# Keg_Cop.net
KiCad netlist of a schematic drawn in EAGLE
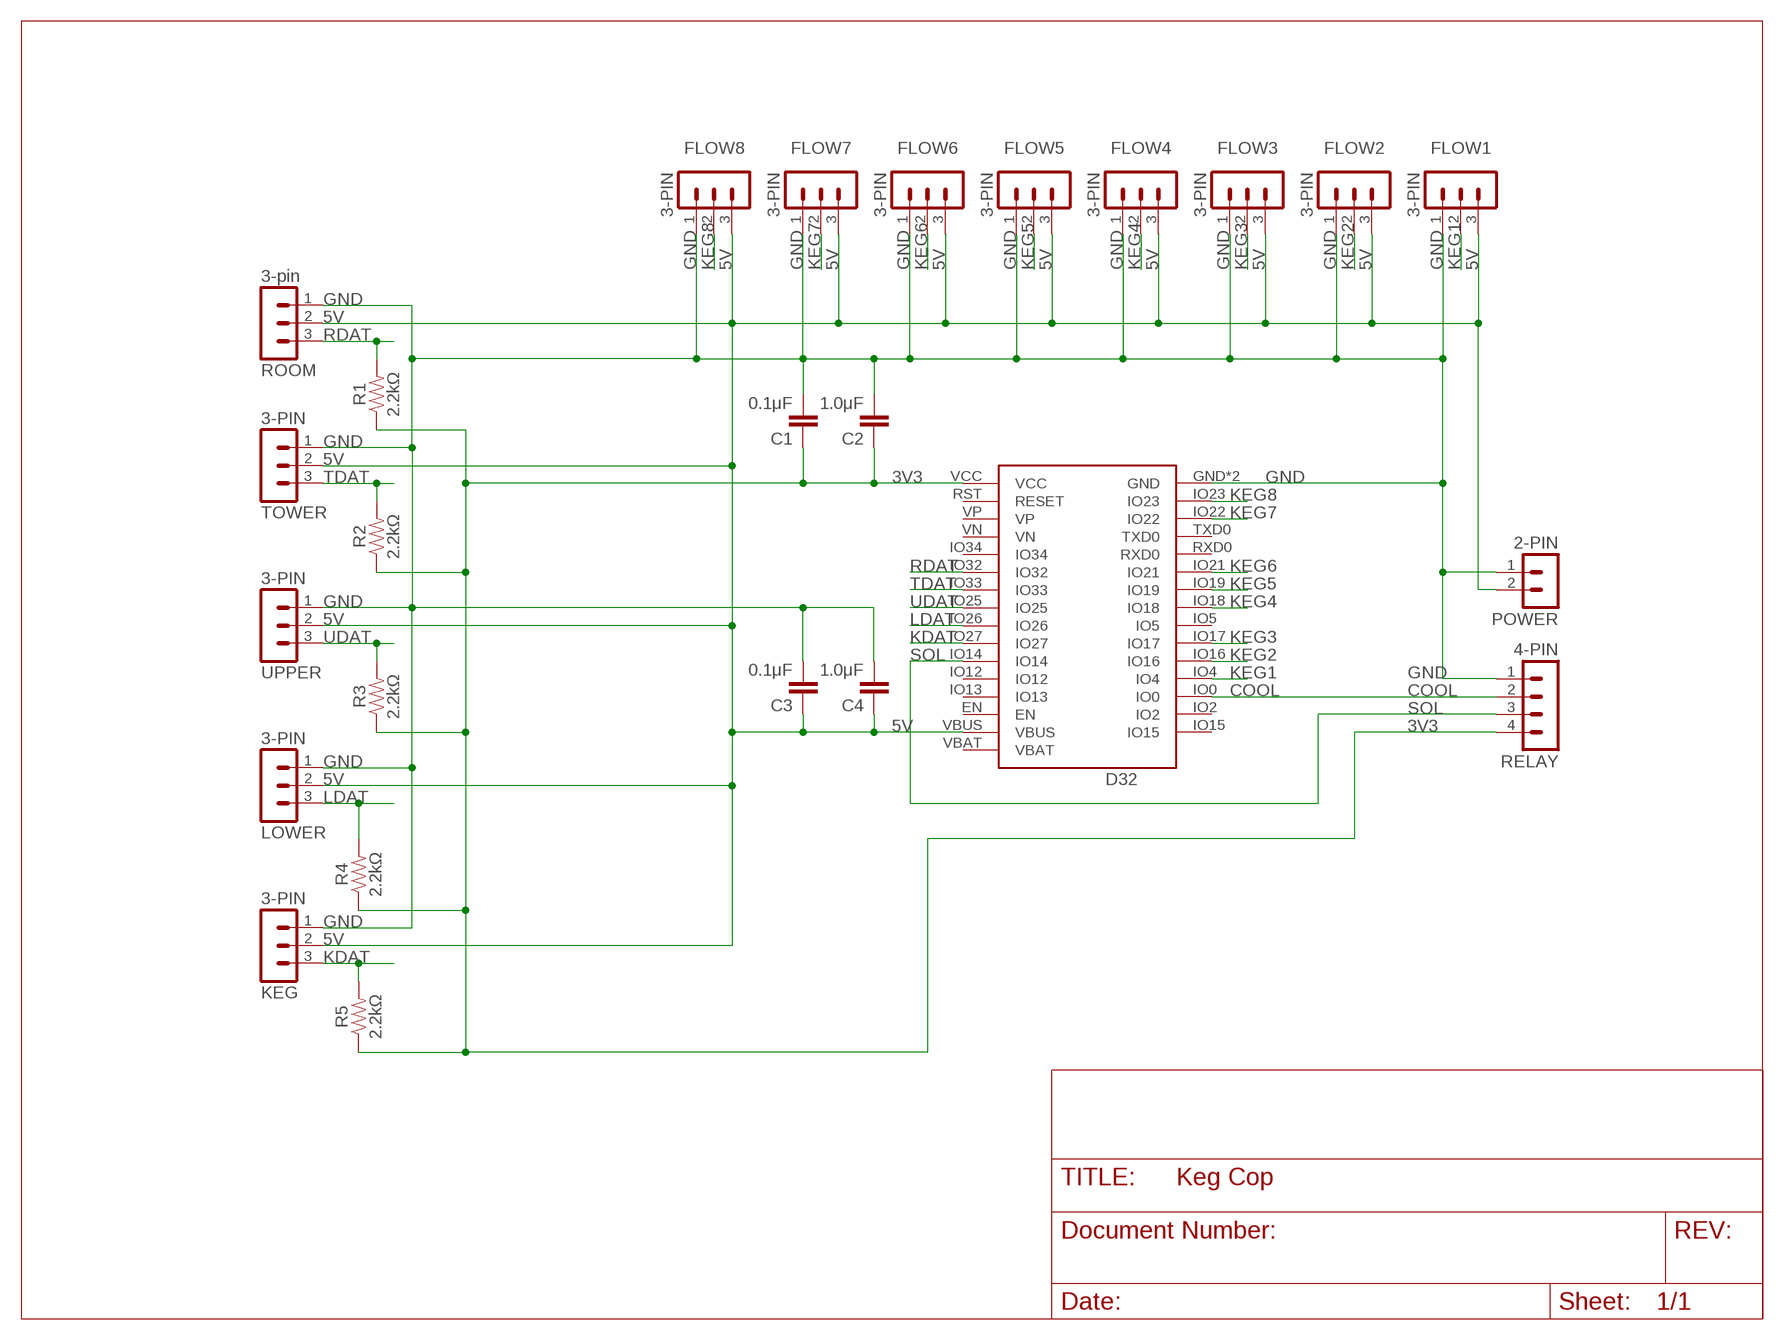
[diagram p0: schematic, sheet 1]

(export (version "E")
  (design (tool "Eeschema 10.0.6"))
  (components
    (comp (ref "C1")
      (value "0.1μF")
      (footprint "eagle-import:CAP_PTH-2.54")
      (libsource (lib "eagle-import") (part "CAP_CERAMIC_2.54"))
    )
    (comp (ref "C2")
      (value "1.0μF")
      (footprint "eagle-import:CAP_PTH-2.54")
      (libsource (lib "eagle-import") (part "CAP_CERAMIC_2.54"))
    )
    (comp (ref "C3")
      (value "0.1μF")
      (footprint "eagle-import:CAP_PTH-2.54")
      (libsource (lib "eagle-import") (part "CAP_CERAMIC_2.54"))
    )
    (comp (ref "C4")
      (value "1.0μF")
      (footprint "eagle-import:CAP_PTH-2.54")
      (libsource (lib "eagle-import") (part "CAP_CERAMIC_2.54"))
    )
    (comp (ref "D32")
      (value "WEMOS-D32D32_NO_BATT")
      (footprint "eagle-import:D32_NO_BATT")
      (libsource (lib "eagle-import") (part "WEMOS-D32D32_NO_BATT"))
    )
    (comp (ref "FLOW1")
      (value "3-PIN")
      (footprint "eagle-import:MA03-1")
      (libsource (lib "eagle-import") (part "MA03-1"))
    )
    (comp (ref "FLOW2")
      (value "3-PIN")
      (footprint "eagle-import:MA03-1")
      (libsource (lib "eagle-import") (part "MA03-1"))
    )
    (comp (ref "FLOW3")
      (value "3-PIN")
      (footprint "eagle-import:MA03-1")
      (libsource (lib "eagle-import") (part "MA03-1"))
    )
    (comp (ref "FLOW4")
      (value "3-PIN")
      (footprint "eagle-import:MA03-1")
      (libsource (lib "eagle-import") (part "MA03-1"))
    )
    (comp (ref "FLOW5")
      (value "3-PIN")
      (footprint "eagle-import:MA03-1")
      (libsource (lib "eagle-import") (part "MA03-1"))
    )
    (comp (ref "FLOW6")
      (value "3-PIN")
      (footprint "eagle-import:MA03-1")
      (libsource (lib "eagle-import") (part "MA03-1"))
    )
    (comp (ref "FLOW7")
      (value "3-PIN")
      (footprint "eagle-import:MA03-1")
      (libsource (lib "eagle-import") (part "MA03-1"))
    )
    (comp (ref "FLOW8")
      (value "3-PIN")
      (footprint "eagle-import:MA03-1")
      (libsource (lib "eagle-import") (part "MA03-1"))
    )
    (comp (ref "KEG")
      (value "3-PIN")
      (footprint "eagle-import:MA03-1")
      (libsource (lib "eagle-import") (part "MA03-1"))
    )
    (comp (ref "LOWER")
      (value "3-PIN")
      (footprint "eagle-import:MA03-1")
      (libsource (lib "eagle-import") (part "MA03-1"))
    )
    (comp (ref "POWER")
      (value "2-PIN")
      (footprint "eagle-import:HDR-2_VERT")
      (libsource (lib "eagle-import") (part "HDR-2"))
    )
    (comp (ref "R1")
      (value "2.2kΩ")
      (footprint "eagle-import:AXIAL-0.3")
      (libsource (lib "eagle-import") (part "RESISTORAXIAL-0.3"))
    )
    (comp (ref "R2")
      (value "2.2kΩ")
      (footprint "eagle-import:AXIAL-0.3")
      (libsource (lib "eagle-import") (part "RESISTORAXIAL-0.3"))
    )
    (comp (ref "R3")
      (value "2.2kΩ")
      (footprint "eagle-import:AXIAL-0.3")
      (libsource (lib "eagle-import") (part "RESISTORAXIAL-0.3"))
    )
    (comp (ref "R4")
      (value "2.2kΩ")
      (footprint "eagle-import:AXIAL-0.3")
      (libsource (lib "eagle-import") (part "RESISTORAXIAL-0.3"))
    )
    (comp (ref "R5")
      (value "2.2kΩ")
      (footprint "eagle-import:AXIAL-0.3")
      (libsource (lib "eagle-import") (part "RESISTORAXIAL-0.3"))
    )
    (comp (ref "RELAY")
      (value "4-PIN")
      (footprint "eagle-import:MA04-1")
      (libsource (lib "eagle-import") (part "MA04-1"))
    )
    (comp (ref "ROOM")
      (value "3-pin")
      (footprint "eagle-import:MA03-1")
      (libsource (lib "eagle-import") (part "MA03-1"))
    )
    (comp (ref "TOWER")
      (value "3-PIN")
      (footprint "eagle-import:MA03-1")
      (libsource (lib "eagle-import") (part "MA03-1"))
    )
    (comp (ref "UPPER")
      (value "3-PIN")
      (footprint "eagle-import:MA03-1")
      (libsource (lib "eagle-import") (part "MA03-1"))
    )
  )
  (nets
    (net (code "1") (name "/3V3") (class "Default")
      (node (ref "C1") (pin "1") (pinfunction "1_1") (pintype "passive"))
      (node (ref "C2") (pin "1") (pinfunction "1_1") (pintype "passive"))
      (node (ref "D32") (pin "VCC") (pinfunction "VCC_VCC") (pintype "power_in"))
      (node (ref "R1") (pin "P$1") (pinfunction "1_P$1") (pintype "passive"))
      (node (ref "R2") (pin "P$1") (pinfunction "1_P$1") (pintype "passive"))
      (node (ref "R3") (pin "P$1") (pinfunction "1_P$1") (pintype "passive"))
      (node (ref "R4") (pin "P$1") (pinfunction "1_P$1") (pintype "passive"))
      (node (ref "R5") (pin "P$1") (pinfunction "1_P$1") (pintype "passive"))
      (node (ref "RELAY") (pin "4") (pinfunction "4_4") (pintype "passive"))
    )
    (net (code "2") (name "/5V") (class "Default")
      (node (ref "C3") (pin "1") (pinfunction "1_1") (pintype "passive"))
      (node (ref "C4") (pin "1") (pinfunction "1_1") (pintype "passive"))
      (node (ref "D32") (pin "VBUS") (pinfunction "VBUS_VBUS") (pintype "bidirectional"))
      (node (ref "FLOW1") (pin "3") (pinfunction "3_3") (pintype "passive"))
      (node (ref "FLOW2") (pin "3") (pinfunction "3_3") (pintype "passive"))
      (node (ref "FLOW3") (pin "3") (pinfunction "3_3") (pintype "passive"))
      (node (ref "FLOW4") (pin "3") (pinfunction "3_3") (pintype "passive"))
      (node (ref "FLOW5") (pin "3") (pinfunction "3_3") (pintype "passive"))
      (node (ref "FLOW6") (pin "3") (pinfunction "3_3") (pintype "passive"))
      (node (ref "FLOW7") (pin "3") (pinfunction "3_3") (pintype "passive"))
      (node (ref "FLOW8") (pin "3") (pinfunction "3_3") (pintype "passive"))
      (node (ref "KEG") (pin "2") (pinfunction "2_2") (pintype "passive"))
      (node (ref "LOWER") (pin "2") (pinfunction "2_2") (pintype "passive"))
      (node (ref "POWER") (pin "2") (pinfunction "2_2") (pintype "passive"))
      (node (ref "ROOM") (pin "2") (pinfunction "2_2") (pintype "passive"))
      (node (ref "TOWER") (pin "2") (pinfunction "2_2") (pintype "passive"))
      (node (ref "UPPER") (pin "2") (pinfunction "2_2") (pintype "passive"))
    )
    (net (code "3") (name "/COOL") (class "Default")
      (node (ref "D32") (pin "IO0") (pinfunction "IO0_IO0") (pintype "bidirectional"))
      (node (ref "RELAY") (pin "2") (pinfunction "2_2") (pintype "passive"))
    )
    (net (code "4") (name "/GND") (class "Default")
      (node (ref "C1") (pin "2") (pinfunction "2_2") (pintype "passive"))
      (node (ref "C2") (pin "2") (pinfunction "2_2") (pintype "passive"))
      (node (ref "C3") (pin "2") (pinfunction "2_2") (pintype "passive"))
      (node (ref "C4") (pin "2") (pinfunction "2_2") (pintype "passive"))
      (node (ref "D32") (pin "GND") (pinfunction "GND_GND") (pintype "power_in"))
      (node (ref "D32") (pin "GND2") (pinfunction "GND_GND2") (pintype "power_in"))
      (node (ref "FLOW1") (pin "1") (pinfunction "1_1") (pintype "passive"))
      (node (ref "FLOW2") (pin "1") (pinfunction "1_1") (pintype "passive"))
      (node (ref "FLOW3") (pin "1") (pinfunction "1_1") (pintype "passive"))
      (node (ref "FLOW4") (pin "1") (pinfunction "1_1") (pintype "passive"))
      (node (ref "FLOW5") (pin "1") (pinfunction "1_1") (pintype "passive"))
      (node (ref "FLOW6") (pin "1") (pinfunction "1_1") (pintype "passive"))
      (node (ref "FLOW7") (pin "1") (pinfunction "1_1") (pintype "passive"))
      (node (ref "FLOW8") (pin "1") (pinfunction "1_1") (pintype "passive"))
      (node (ref "KEG") (pin "1") (pinfunction "1_1") (pintype "passive"))
      (node (ref "LOWER") (pin "1") (pinfunction "1_1") (pintype "passive"))
      (node (ref "POWER") (pin "1") (pinfunction "1_1") (pintype "passive"))
      (node (ref "RELAY") (pin "1") (pinfunction "1_1") (pintype "passive"))
      (node (ref "ROOM") (pin "1") (pinfunction "1_1") (pintype "passive"))
      (node (ref "TOWER") (pin "1") (pinfunction "1_1") (pintype "passive"))
      (node (ref "UPPER") (pin "1") (pinfunction "1_1") (pintype "passive"))
    )
    (net (code "5") (name "/KDAT") (class "Default")
      (node (ref "D32") (pin "IO27") (pinfunction "IO27_IO27") (pintype "bidirectional"))
      (node (ref "KEG") (pin "3") (pinfunction "3_3") (pintype "passive"))
      (node (ref "R5") (pin "P$2") (pinfunction "2_P$2") (pintype "passive"))
    )
    (net (code "6") (name "/KEG1") (class "Default")
      (node (ref "D32") (pin "IO4") (pinfunction "IO4_IO4") (pintype "bidirectional"))
      (node (ref "FLOW1") (pin "2") (pinfunction "2_2") (pintype "passive"))
    )
    (net (code "7") (name "/KEG2") (class "Default")
      (node (ref "D32") (pin "IO16") (pinfunction "IO16_IO16") (pintype "bidirectional"))
      (node (ref "FLOW2") (pin "2") (pinfunction "2_2") (pintype "passive"))
    )
    (net (code "8") (name "/KEG3") (class "Default")
      (node (ref "D32") (pin "IO17") (pinfunction "IO17_IO17") (pintype "bidirectional"))
      (node (ref "FLOW3") (pin "2") (pinfunction "2_2") (pintype "passive"))
    )
    (net (code "9") (name "/KEG4") (class "Default")
      (node (ref "D32") (pin "IO18") (pinfunction "IO18_IO18") (pintype "bidirectional"))
      (node (ref "FLOW4") (pin "2") (pinfunction "2_2") (pintype "passive"))
    )
    (net (code "10") (name "/KEG5") (class "Default")
      (node (ref "D32") (pin "IO19") (pinfunction "IO19_IO19") (pintype "bidirectional"))
      (node (ref "FLOW5") (pin "2") (pinfunction "2_2") (pintype "passive"))
    )
    (net (code "11") (name "/KEG6") (class "Default")
      (node (ref "D32") (pin "IO21") (pinfunction "IO21_IO21") (pintype "bidirectional"))
      (node (ref "FLOW6") (pin "2") (pinfunction "2_2") (pintype "passive"))
    )
    (net (code "12") (name "/KEG7") (class "Default")
      (node (ref "D32") (pin "IO22") (pinfunction "IO22_IO22") (pintype "bidirectional"))
      (node (ref "FLOW7") (pin "2") (pinfunction "2_2") (pintype "passive"))
    )
    (net (code "13") (name "/KEG8") (class "Default")
      (node (ref "D32") (pin "IO23") (pinfunction "IO23_IO23") (pintype "bidirectional"))
      (node (ref "FLOW8") (pin "2") (pinfunction "2_2") (pintype "passive"))
    )
    (net (code "14") (name "/LDAT") (class "Default")
      (node (ref "D32") (pin "IO26") (pinfunction "IO26_IO26") (pintype "bidirectional"))
      (node (ref "LOWER") (pin "3") (pinfunction "3_3") (pintype "passive"))
      (node (ref "R4") (pin "P$2") (pinfunction "2_P$2") (pintype "passive"))
    )
    (net (code "15") (name "/RDAT") (class "Default")
      (node (ref "D32") (pin "IO32") (pinfunction "IO32_IO32") (pintype "bidirectional"))
      (node (ref "R1") (pin "P$2") (pinfunction "2_P$2") (pintype "passive"))
      (node (ref "ROOM") (pin "3") (pinfunction "3_3") (pintype "passive"))
    )
    (net (code "16") (name "/SOL") (class "Default")
      (node (ref "D32") (pin "IO14") (pinfunction "IO14_IO14") (pintype "bidirectional"))
      (node (ref "RELAY") (pin "3") (pinfunction "3_3") (pintype "passive"))
    )
    (net (code "17") (name "/TDAT") (class "Default")
      (node (ref "D32") (pin "IO33") (pinfunction "IO33_IO33") (pintype "bidirectional"))
      (node (ref "R2") (pin "P$2") (pinfunction "2_P$2") (pintype "passive"))
      (node (ref "TOWER") (pin "3") (pinfunction "3_3") (pintype "passive"))
    )
    (net (code "18") (name "/UDAT") (class "Default")
      (node (ref "D32") (pin "IO25") (pinfunction "IO25_IO25") (pintype "bidirectional"))
      (node (ref "R3") (pin "P$2") (pinfunction "2_P$2") (pintype "passive"))
      (node (ref "UPPER") (pin "3") (pinfunction "3_3") (pintype "passive"))
    )
    (net (code "19") (name "unconnected-(D32-PadEN)") (class "Default")
      (node (ref "D32") (pin "EN") (pinfunction "EN_EN") (pintype "bidirectional"))
    )
    (net (code "20") (name "unconnected-(D32-PadIO2)") (class "Default")
      (node (ref "D32") (pin "IO2") (pinfunction "IO2_IO2") (pintype "bidirectional"))
    )
    (net (code "21") (name "unconnected-(D32-PadIO5)") (class "Default")
      (node (ref "D32") (pin "IO5") (pinfunction "IO5_IO5") (pintype "bidirectional"))
    )
    (net (code "22") (name "unconnected-(D32-PadIO12)") (class "Default")
      (node (ref "D32") (pin "IO12") (pinfunction "IO12_IO12") (pintype "bidirectional"))
    )
    (net (code "23") (name "unconnected-(D32-PadIO13)") (class "Default")
      (node (ref "D32") (pin "IO13") (pinfunction "IO13_IO13") (pintype "bidirectional"))
    )
    (net (code "24") (name "unconnected-(D32-PadIO15)") (class "Default")
      (node (ref "D32") (pin "IO15") (pinfunction "IO15_IO15") (pintype "bidirectional"))
    )
    (net (code "25") (name "unconnected-(D32-PadIO34)") (class "Default")
      (node (ref "D32") (pin "IO34") (pinfunction "IO34_IO34") (pintype "bidirectional"))
    )
    (net (code "26") (name "unconnected-(D32-PadRXD0)") (class "Default")
      (node (ref "D32") (pin "RXD0") (pinfunction "RXD0_RXD0") (pintype "input"))
    )
    (net (code "27") (name "unconnected-(D32-PadTXD0)") (class "Default")
      (node (ref "D32") (pin "TXD0") (pinfunction "TXD0_TXD0") (pintype "output"))
    )
    (net (code "28") (name "unconnected-(D32-PadVBAT)") (class "Default")
      (node (ref "D32") (pin "VBAT") (pinfunction "VBAT_VBAT") (pintype "bidirectional"))
    )
    (net (code "29") (name "unconnected-(D32-PadVN)") (class "Default")
      (node (ref "D32") (pin "VN") (pinfunction "VN_VN") (pintype "bidirectional"))
    )
    (net (code "30") (name "unconnected-(D32-PadVP)") (class "Default")
      (node (ref "D32") (pin "VP") (pinfunction "VP_VP") (pintype "bidirectional"))
    )
    (net (code "31") (name "unconnected-(D32-RESET-PadRST)") (class "Default")
      (node (ref "D32") (pin "RST") (pinfunction "RESET_RST") (pintype "bidirectional"))
    )
  )
)
